# New_Project_2025-11-05_14-04-50.net
KiCad netlist of a schematic drawn in EasyEDA Pro
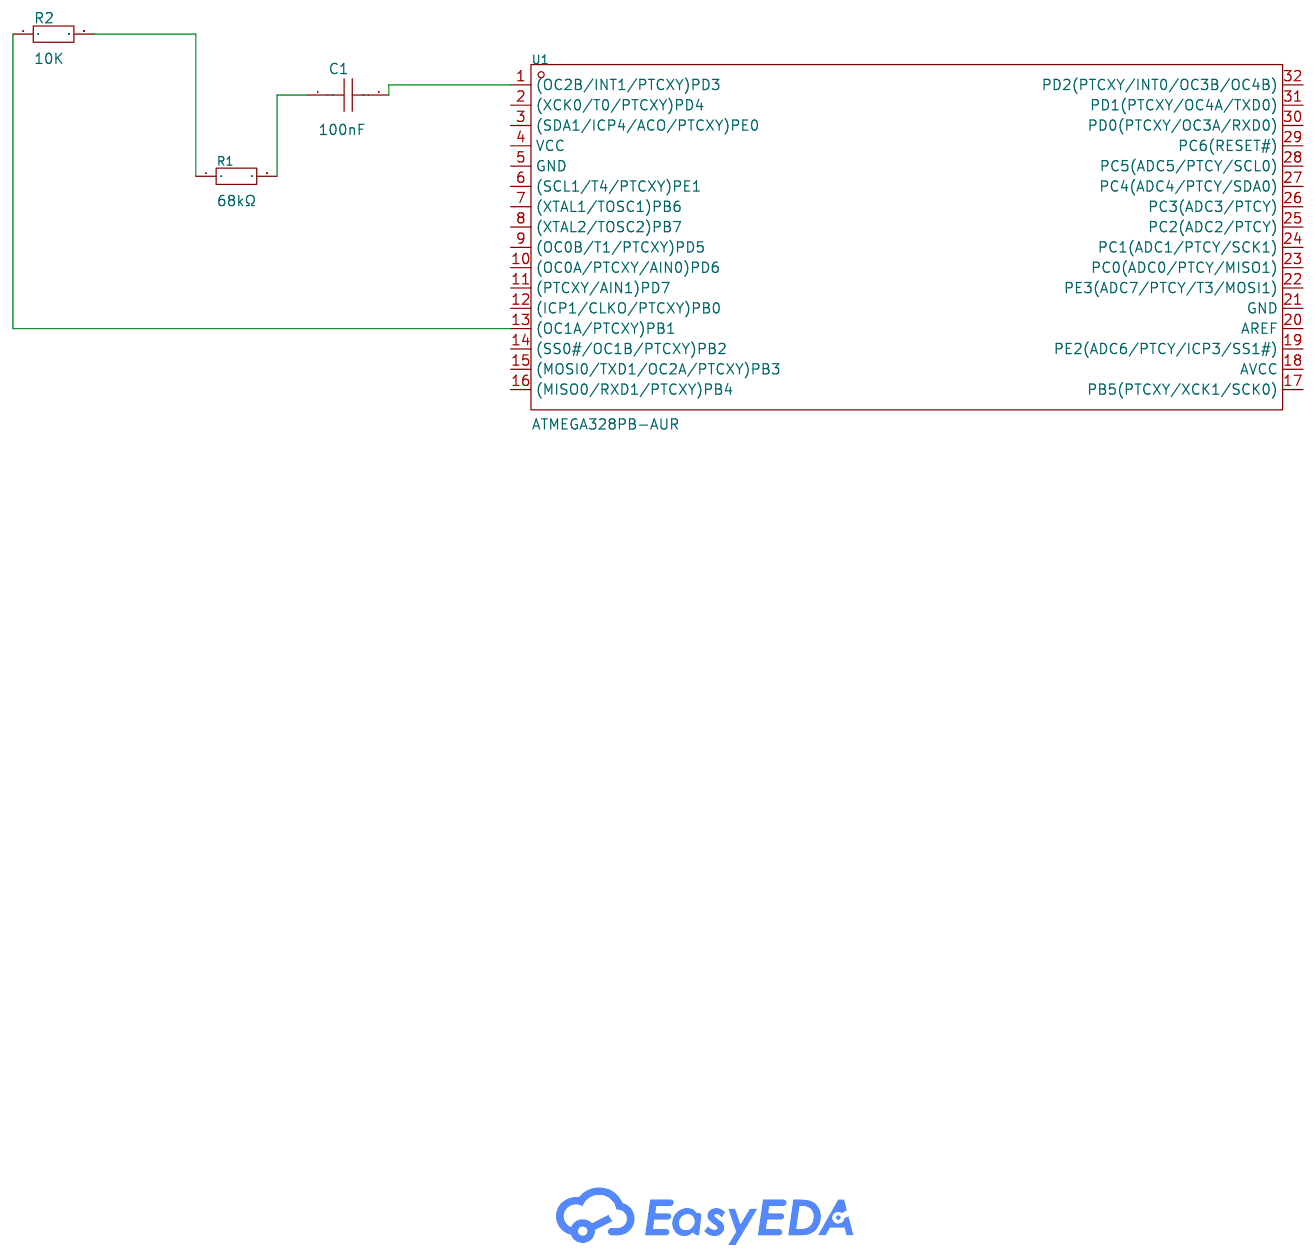
[diagram p0: schematic sheet]

(export (version "E")
  (design (tool "Eeschema 10.0.6"))
  (components
    (comp (ref "C1")
      (value "100nF")
      (footprint "easyedapro:C0603")
      (description "Capacitance:100nF Tolerance:±10% Tolerance:±10% Voltage Rating:50V Temperature Coefficient:X7R")
      (fields
        (field (name "Manufacturer Part") "CC0603KRX7R9BB104")
        (field (name "Manufacturer") "YAGEO(国巨)")
      )
      (libsource (lib "easyedapro") (part "CC0603KRX7R9BB104"))
    )
    (comp (ref "R1")
      (value "68kΩ")
      (footprint "easyedapro:R0603")
      (fields
        (field (name "Manufacturer Part") "0603WAF6802T5E")
        (field (name "Manufacturer") "UNI-ROYAL(厚声)")
      )
      (libsource (lib "easyedapro") (part "0603WAF6802T5E"))
    )
    (comp (ref "R2") (value "10K") (footprint "easyedapro:R0603") (libsource (lib "easyedapro") (part "Res")))
    (comp (ref "U1")
      (value "ATMEGA328PB-AUR")
      (footprint "easyedapro:TQFP-32_L7.0-W7.0-P0.80-LS9.0-BL")
      (fields (field (name "Manufacturer") "MICROCHIP(美国微芯)"))
      (libsource (lib "easyedapro") (part "ATMEGA328PB-AUR"))
    )
  )
  (nets
    (net (code "1") (name "Net-(C1-Pad1)") (class "Default")
      (node (ref "C1") (pin "1") (pinfunction "1_1") (pintype "unspecified"))
      (node (ref "R1") (pin "2") (pinfunction "2_2") (pintype "input"))
    )
    (net (code "2") (name "Net-(R1-Pad1)") (class "Default")
      (node (ref "R1") (pin "1") (pinfunction "1_1") (pintype "input"))
      (node (ref "R2") (pin "2") (pinfunction "2_2") (pintype "input"))
    )
    (net (code "3") (name "Net-(U1-(OC1A{slash}PTCXY)PB1)") (class "Default")
      (node (ref "R2") (pin "1") (pinfunction "1_1") (pintype "input"))
      (node (ref "U1") (pin "13") (pinfunction "(OC1A/PTCXY)PB1_13") (pintype "input"))
    )
    (net (code "4") (name "Net-(U1-(OC2B{slash}INT1{slash}PTCXY)PD3)") (class "Default")
      (node (ref "C1") (pin "2") (pinfunction "2_2") (pintype "unspecified"))
      (node (ref "U1") (pin "1") (pinfunction "(OC2B/INT1/PTCXY)PD3_1") (pintype "input"))
    )
    (net (code "5") (name "unconnected-(U1-(ICP1{slash}CLKO{slash}PTCXY)PB0-Pad12)") (class "Default")
      (node (ref "U1") (pin "12") (pinfunction "(ICP1/CLKO/PTCXY)PB0_12") (pintype "input"))
    )
    (net (code "6") (name "unconnected-(U1-(MISO0{slash}RXD1{slash}PTCXY)PB4-Pad16)") (class "Default")
      (node (ref "U1") (pin "16") (pinfunction "(MISO0/RXD1/PTCXY)PB4_16") (pintype "input"))
    )
    (net (code "7") (name "unconnected-(U1-(MOSI0{slash}TXD1{slash}OC2A{slash}PTCXY)PB3-Pad15)") (class "Default")
      (node (ref "U1") (pin "15") (pinfunction "(MOSI0/TXD1/OC2A/PTCXY)PB3_15") (pintype "input"))
    )
    (net (code "8") (name "unconnected-(U1-(OC0A{slash}PTCXY{slash}AIN0)PD6-Pad10)") (class "Default")
      (node (ref "U1") (pin "10") (pinfunction "(OC0A/PTCXY/AIN0)PD6_10") (pintype "input"))
    )
    (net (code "9") (name "unconnected-(U1-(OC0B{slash}T1{slash}PTCXY)PD5-Pad9)") (class "Default")
      (node (ref "U1") (pin "9") (pinfunction "(OC0B/T1/PTCXY)PD5_9") (pintype "input"))
    )
    (net (code "10") (name "unconnected-(U1-(PTCXY{slash}AIN1)PD7-Pad11)") (class "Default")
      (node (ref "U1") (pin "11") (pinfunction "(PTCXY/AIN1)PD7_11") (pintype "input"))
    )
    (net (code "11") (name "unconnected-(U1-(SCL1{slash}T4{slash}PTCXY)PE1-Pad6)") (class "Default")
      (node (ref "U1") (pin "6") (pinfunction "(SCL1/T4/PTCXY)PE1_6") (pintype "input"))
    )
    (net (code "12") (name "unconnected-(U1-(SDA1{slash}ICP4{slash}ACO{slash}PTCXY)PE0-Pad3)") (class "Default")
      (node (ref "U1") (pin "3") (pinfunction "(SDA1/ICP4/ACO/PTCXY)PE0_3") (pintype "input"))
    )
    (net (code "13") (name "unconnected-(U1-(SS0#{slash}OC1B{slash}PTCXY)PB2-Pad14)") (class "Default")
      (node (ref "U1") (pin "14") (pinfunction "(SS0#/OC1B/PTCXY)PB2_14") (pintype "input"))
    )
    (net (code "14") (name "unconnected-(U1-(XCK0{slash}T0{slash}PTCXY)PD4-Pad2)") (class "Default")
      (node (ref "U1") (pin "2") (pinfunction "(XCK0/T0/PTCXY)PD4_2") (pintype "input"))
    )
    (net (code "15") (name "unconnected-(U1-(XTAL1{slash}TOSC1)PB6-Pad7)") (class "Default")
      (node (ref "U1") (pin "7") (pinfunction "(XTAL1/TOSC1)PB6_7") (pintype "input"))
    )
    (net (code "16") (name "unconnected-(U1-(XTAL2{slash}TOSC2)PB7-Pad8)") (class "Default")
      (node (ref "U1") (pin "8") (pinfunction "(XTAL2/TOSC2)PB7_8") (pintype "input"))
    )
    (net (code "17") (name "unconnected-(U1-AREF-Pad20)") (class "Default")
      (node (ref "U1") (pin "20") (pinfunction "AREF_20") (pintype "input"))
    )
    (net (code "18") (name "unconnected-(U1-AVCC-Pad18)") (class "Default")
      (node (ref "U1") (pin "18") (pinfunction "AVCC_18") (pintype "input"))
    )
    (net (code "19") (name "unconnected-(U1-GND-Pad5)") (class "Default")
      (node (ref "U1") (pin "5") (pinfunction "GND_5") (pintype "input"))
    )
    (net (code "20") (name "unconnected-(U1-GND-Pad21)") (class "Default")
      (node (ref "U1") (pin "21") (pinfunction "GND_21") (pintype "input"))
    )
    (net (code "21") (name "unconnected-(U1-PB5(PTCXY{slash}XCK1{slash}SCK0)-Pad17)") (class "Default")
      (node (ref "U1") (pin "17") (pinfunction "PB5(PTCXY/XCK1/SCK0)_17") (pintype "input"))
    )
    (net (code "22") (name "unconnected-(U1-PC0(ADC0{slash}PTCY{slash}MISO1)-Pad23)") (class "Default")
      (node (ref "U1") (pin "23") (pinfunction "PC0(ADC0/PTCY/MISO1)_23") (pintype "input"))
    )
    (net (code "23") (name "unconnected-(U1-PC1(ADC1{slash}PTCY{slash}SCK1)-Pad24)") (class "Default")
      (node (ref "U1") (pin "24") (pinfunction "PC1(ADC1/PTCY/SCK1)_24") (pintype "input"))
    )
    (net (code "24") (name "unconnected-(U1-PC2(ADC2{slash}PTCY)-Pad25)") (class "Default")
      (node (ref "U1") (pin "25") (pinfunction "PC2(ADC2/PTCY)_25") (pintype "input"))
    )
    (net (code "25") (name "unconnected-(U1-PC3(ADC3{slash}PTCY)-Pad26)") (class "Default")
      (node (ref "U1") (pin "26") (pinfunction "PC3(ADC3/PTCY)_26") (pintype "input"))
    )
    (net (code "26") (name "unconnected-(U1-PC4(ADC4{slash}PTCY{slash}SDA0)-Pad27)") (class "Default")
      (node (ref "U1") (pin "27") (pinfunction "PC4(ADC4/PTCY/SDA0)_27") (pintype "input"))
    )
    (net (code "27") (name "unconnected-(U1-PC5(ADC5{slash}PTCY{slash}SCL0)-Pad28)") (class "Default")
      (node (ref "U1") (pin "28") (pinfunction "PC5(ADC5/PTCY/SCL0)_28") (pintype "input"))
    )
    (net (code "28") (name "unconnected-(U1-PC6(RESET#)-Pad29)") (class "Default")
      (node (ref "U1") (pin "29") (pinfunction "PC6(RESET#)_29") (pintype "input"))
    )
    (net (code "29") (name "unconnected-(U1-PD0(PTCXY{slash}OC3A{slash}RXD0)-Pad30)") (class "Default")
      (node (ref "U1") (pin "30") (pinfunction "PD0(PTCXY/OC3A/RXD0)_30") (pintype "input"))
    )
    (net (code "30") (name "unconnected-(U1-PD1(PTCXY{slash}OC4A{slash}TXD0)-Pad31)") (class "Default")
      (node (ref "U1") (pin "31") (pinfunction "PD1(PTCXY/OC4A/TXD0)_31") (pintype "input"))
    )
    (net (code "31") (name "unconnected-(U1-PD2(PTCXY{slash}INT0{slash}OC3B{slash}OC4B)-Pad32)") (class "Default")
      (node (ref "U1") (pin "32") (pinfunction "PD2(PTCXY/INT0/OC3B/OC4B)_32") (pintype "input"))
    )
    (net (code "32") (name "unconnected-(U1-PE2(ADC6{slash}PTCY{slash}ICP3{slash}SS1#)-Pad19)") (class "Default")
      (node (ref "U1") (pin "19") (pinfunction "PE2(ADC6/PTCY/ICP3/SS1#)_19") (pintype "input"))
    )
    (net (code "33") (name "unconnected-(U1-PE3(ADC7{slash}PTCY{slash}T3{slash}MOSI1)-Pad22)") (class "Default")
      (node (ref "U1") (pin "22") (pinfunction "PE3(ADC7/PTCY/T3/MOSI1)_22") (pintype "input"))
    )
    (net (code "34") (name "unconnected-(U1-VCC-Pad4)") (class "Default")
      (node (ref "U1") (pin "4") (pinfunction "VCC_4") (pintype "input"))
    )
  )
)
